# KMO_IO_MV4.net
KiCad netlist of a schematic drawn in EAGLE
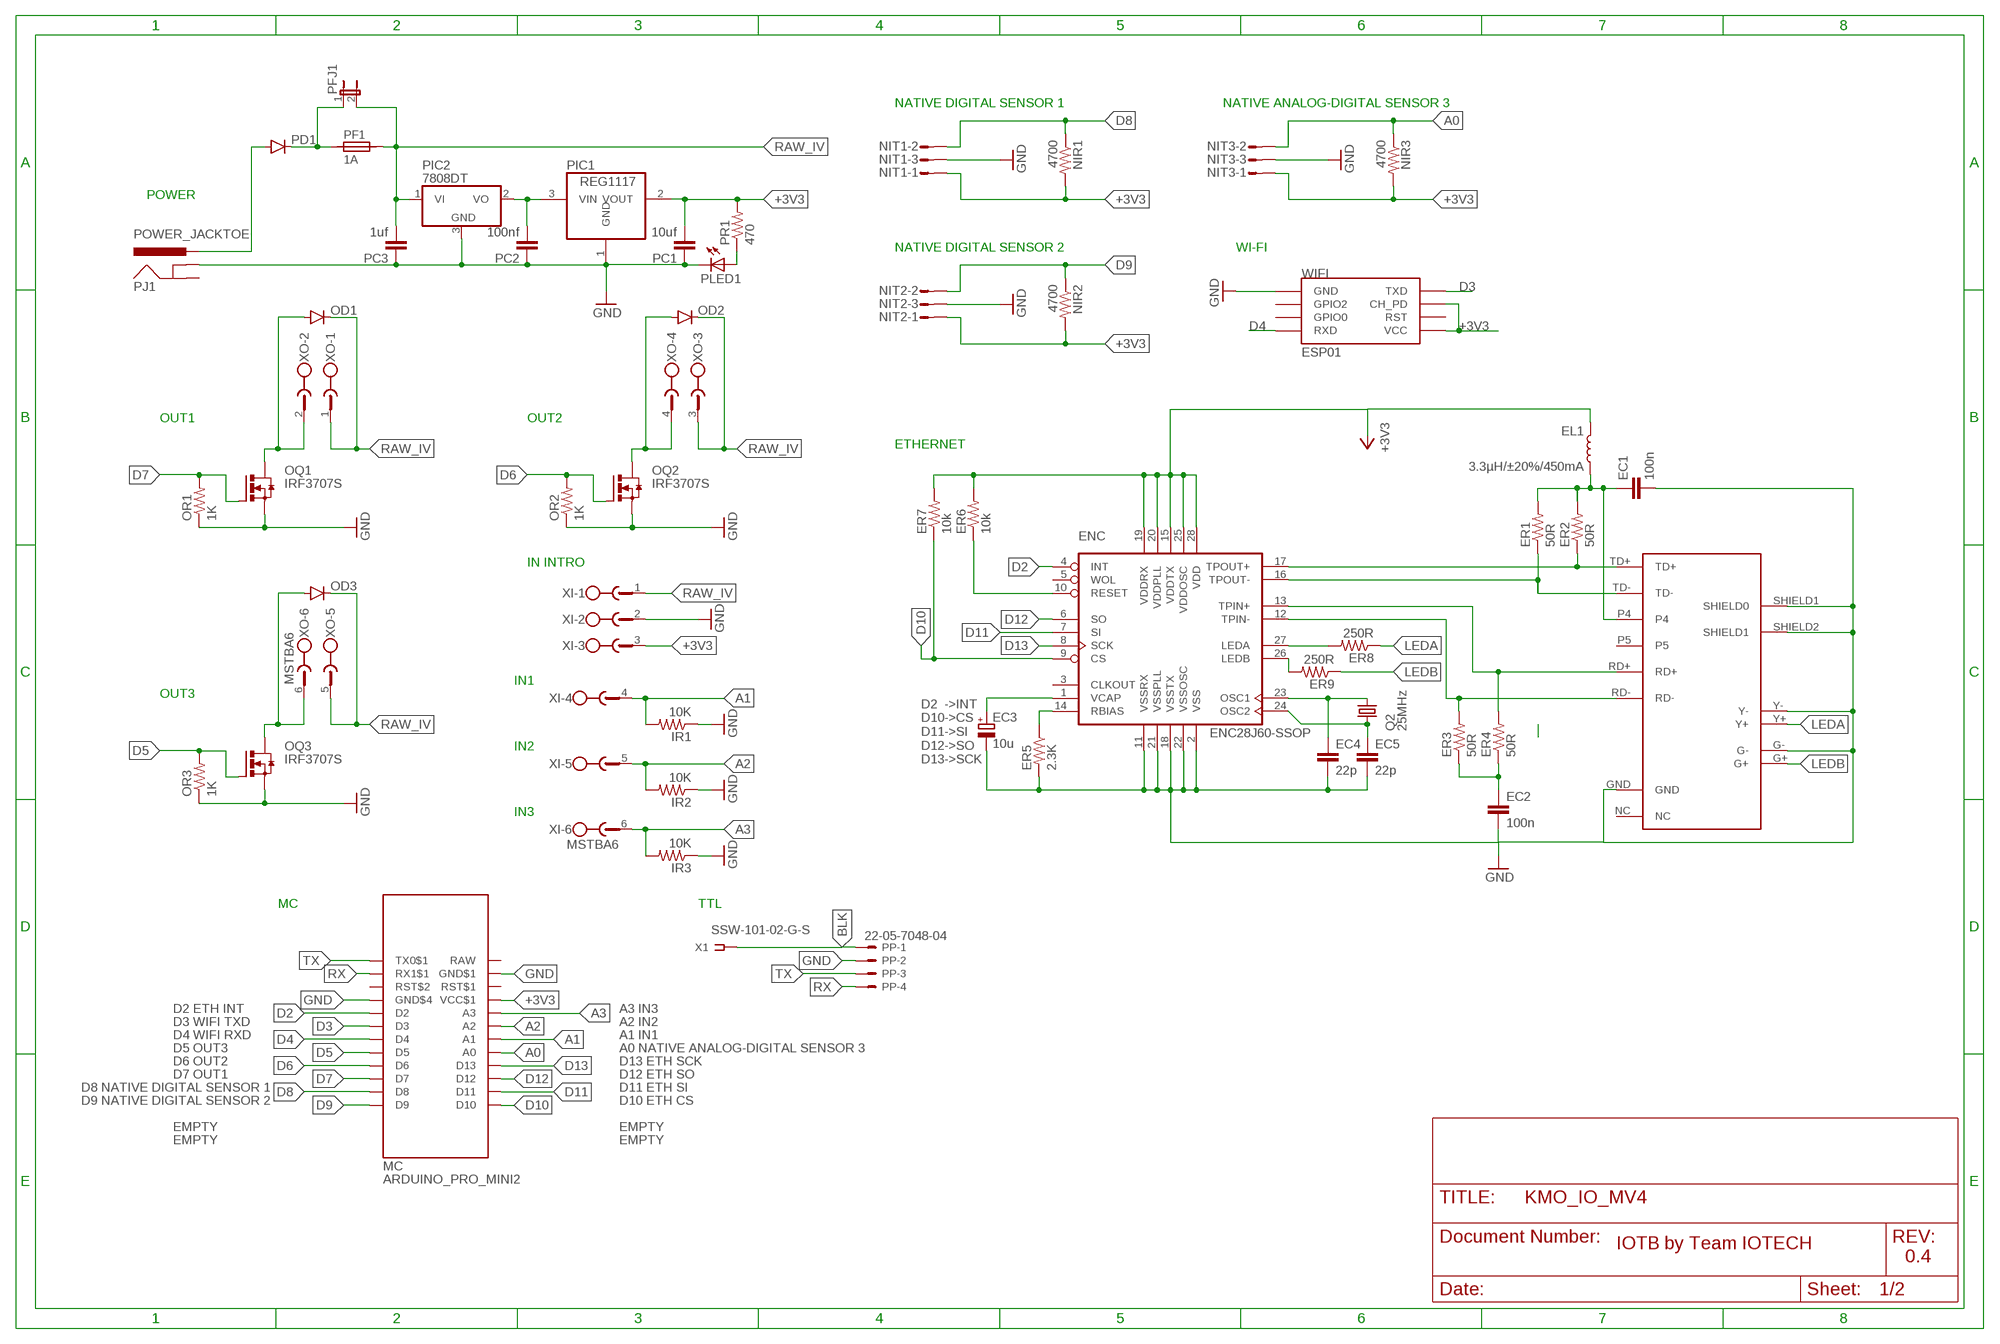
[diagram p0: schematic, sheet 1]
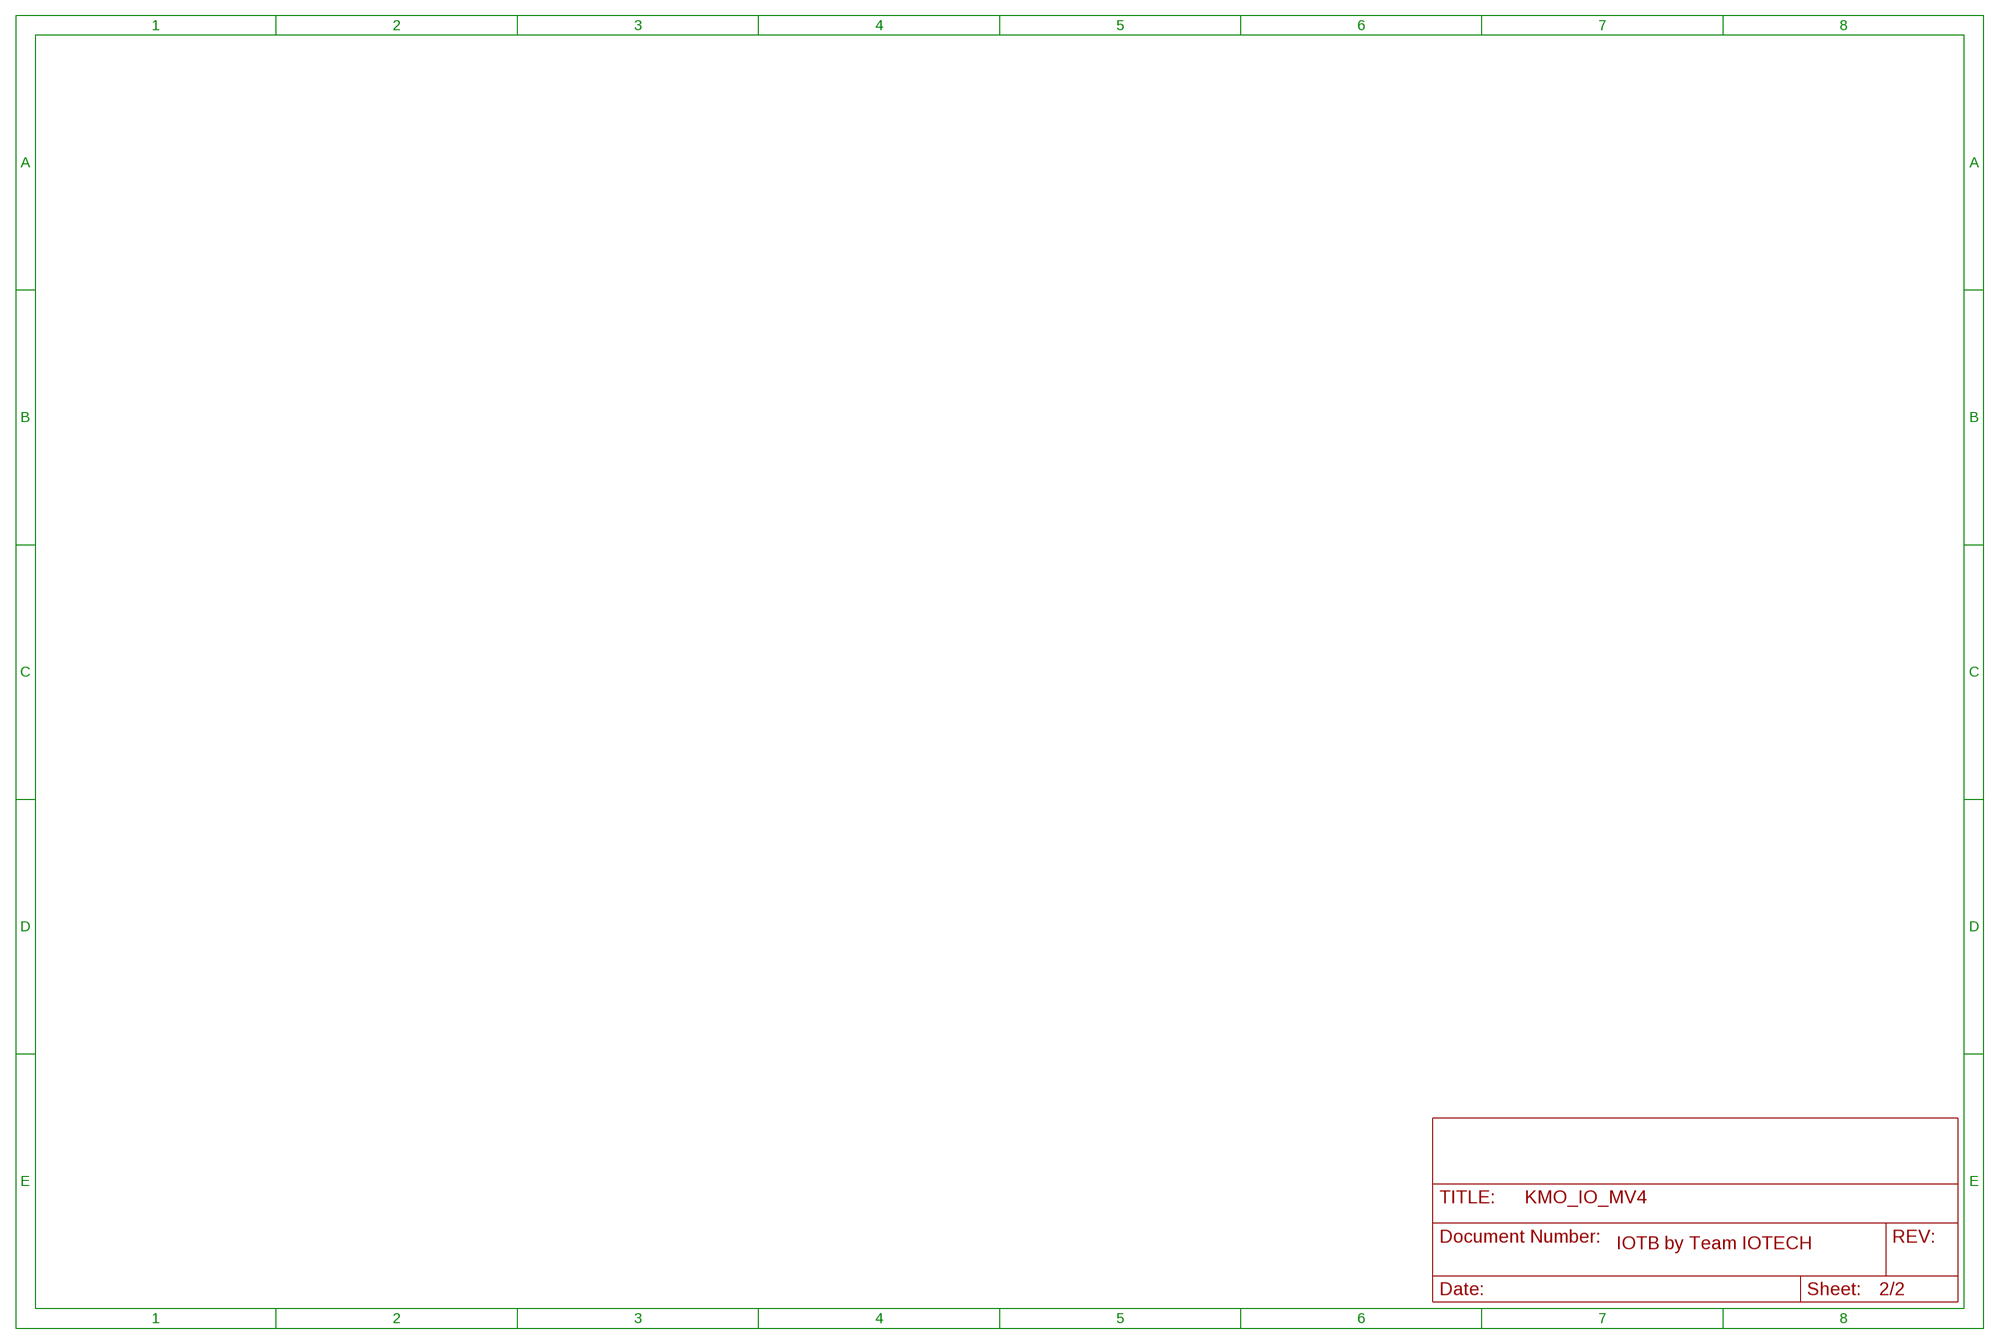
[diagram p1: schematic, sheet 2]

(export (version "E")
  (design (tool "Eeschema 10.0.6"))
  (components
    (comp (ref "EC1")
      (value "100n")
      (footprint "eagle-import:0805")
      (libsource (lib "eagle-import") (part "SparkFun-Passives_CAP0805"))
    )
    (comp (ref "EC2")
      (value "100n")
      (footprint "eagle-import:0805")
      (libsource (lib "eagle-import") (part "SparkFun-Passives_CAP0805"))
    )
    (comp (ref "EC3")
      (value "10u")
      (footprint "eagle-import:SANYO-OSCON_SMD_B6")
      (libsource (lib "eagle-import") (part "CPOL-EUSANYO_SMD_B6"))
    )
    (comp (ref "EC4")
      (value "22p")
      (footprint "eagle-import:0805")
      (libsource (lib "eagle-import") (part "SparkFun-Passives_CAP0805"))
    )
    (comp (ref "EC5")
      (value "22p")
      (footprint "eagle-import:0805")
      (libsource (lib "eagle-import") (part "SparkFun-Passives_CAP0805"))
    )
    (comp (ref "EL1")
      (value "3.3µH/±20%/450mA")
      (footprint "eagle-import:0805")
      (libsource (lib "eagle-import") (part "INDUCTOR-0805-3.3UH"))
    )
    (comp (ref "ENC")
      (value "ENC28J60-SSOP")
      (footprint "eagle-import:SSOP28")
      (libsource (lib "eagle-import") (part "ENC28J60-SSOP"))
    )
    (comp (ref "ER1")
      (value "50R")
      (footprint "eagle-import:0805")
      (libsource (lib "eagle-import") (part "RESISTOR0805-RES"))
    )
    (comp (ref "ER2")
      (value "50R")
      (footprint "eagle-import:0805")
      (libsource (lib "eagle-import") (part "RESISTOR0805-RES"))
    )
    (comp (ref "ER3")
      (value "50R")
      (footprint "eagle-import:0805")
      (libsource (lib "eagle-import") (part "RESISTOR0805-RES"))
    )
    (comp (ref "ER4")
      (value "50R")
      (footprint "eagle-import:0805")
      (libsource (lib "eagle-import") (part "RESISTOR0805-RES"))
    )
    (comp (ref "ER5")
      (value "2.3K")
      (footprint "eagle-import:0805")
      (libsource (lib "eagle-import") (part "RESISTOR0805-RES"))
    )
    (comp (ref "ER6")
      (value "10k")
      (footprint "eagle-import:0805")
      (libsource (lib "eagle-import") (part "RESISTOR0805-RES"))
    )
    (comp (ref "ER7")
      (value "10k")
      (footprint "eagle-import:0805")
      (libsource (lib "eagle-import") (part "RESISTOR0805-RES"))
    )
    (comp (ref "ER8")
      (value "250R")
      (footprint "eagle-import:0805")
      (libsource (lib "eagle-import") (part "RESISTOR0805-RES"))
    )
    (comp (ref "ER9")
      (value "250R")
      (footprint "eagle-import:0805")
      (libsource (lib "eagle-import") (part "RESISTOR0805-RES"))
    )
    (comp (ref "IR1")
      (value "10K")
      (footprint "eagle-import:0805")
      (libsource (lib "eagle-import") (part "RESISTOR0805-RES"))
    )
    (comp (ref "IR2")
      (value "10K")
      (footprint "eagle-import:0805")
      (libsource (lib "eagle-import") (part "RESISTOR0805-RES"))
    )
    (comp (ref "IR3")
      (value "10K")
      (footprint "eagle-import:0805")
      (libsource (lib "eagle-import") (part "RESISTOR0805-RES"))
    )
    (comp (ref "MC")
      (value "ARDUINO_PRO_MINI2")
      (footprint "eagle-import:ARDUINO_PRO_MINI2")
      (libsource (lib "eagle-import") (part "ARDUINO_PRO_MINI2"))
    )
    (comp (ref "NIR1")
      (value "4700")
      (footprint "eagle-import:0805")
      (libsource (lib "eagle-import") (part "RESISTOR0805-RES"))
    )
    (comp (ref "NIR2")
      (value "4700")
      (footprint "eagle-import:0805")
      (libsource (lib "eagle-import") (part "RESISTOR0805-RES"))
    )
    (comp (ref "NIR3")
      (value "4700")
      (footprint "eagle-import:0805")
      (libsource (lib "eagle-import") (part "RESISTOR0805-RES"))
    )
    (comp (ref "NIT1")
      (value "S03P")
      (footprint "eagle-import:S03P")
      (libsource (lib "eagle-import") (part "S03P"))
    )
    (comp (ref "NIT2")
      (value "S03P")
      (footprint "eagle-import:S03P")
      (libsource (lib "eagle-import") (part "S03P"))
    )
    (comp (ref "NIT3")
      (value "S03P")
      (footprint "eagle-import:S03P")
      (libsource (lib "eagle-import") (part "S03P"))
    )
    (comp (ref "OD1")
      (value "DIODESMA")
      (footprint "eagle-import:SMA-DIODE")
      (libsource (lib "eagle-import") (part "DIODESMA"))
    )
    (comp (ref "OD2")
      (value "DIODESMA")
      (footprint "eagle-import:SMA-DIODE")
      (libsource (lib "eagle-import") (part "DIODESMA"))
    )
    (comp (ref "OD3")
      (value "DIODESMA")
      (footprint "eagle-import:SMA-DIODE")
      (libsource (lib "eagle-import") (part "DIODESMA"))
    )
    (comp (ref "OQ1")
      (value "IRF3707S")
      (footprint "eagle-import:D2PACK")
      (libsource (lib "eagle-import") (part "IRF3704S"))
    )
    (comp (ref "OQ2")
      (value "IRF3707S")
      (footprint "eagle-import:D2PACK")
      (libsource (lib "eagle-import") (part "IRF3704S"))
    )
    (comp (ref "OQ3")
      (value "IRF3707S")
      (footprint "eagle-import:D2PACK")
      (libsource (lib "eagle-import") (part "IRF3704S"))
    )
    (comp (ref "OR1")
      (value "1K")
      (footprint "eagle-import:0805")
      (libsource (lib "eagle-import") (part "RESISTOR0805-RES"))
    )
    (comp (ref "OR2")
      (value "1K")
      (footprint "eagle-import:0805")
      (libsource (lib "eagle-import") (part "RESISTOR0805-RES"))
    )
    (comp (ref "OR3")
      (value "1K")
      (footprint "eagle-import:0805")
      (libsource (lib "eagle-import") (part "RESISTOR0805-RES"))
    )
    (comp (ref "PC1")
      (value "10uf")
      (footprint "eagle-import:0805")
      (libsource (lib "eagle-import") (part "CAP0805"))
    )
    (comp (ref "PC2")
      (value "100nf")
      (footprint "eagle-import:0805")
      (libsource (lib "eagle-import") (part "CAP0805"))
    )
    (comp (ref "PC3")
      (value "1uf")
      (footprint "eagle-import:0805")
      (libsource (lib "eagle-import") (part "CAP0805"))
    )
    (comp (ref "PD1")
      (value "DIODESMA")
      (footprint "eagle-import:SMA-DIODE")
      (libsource (lib "eagle-import") (part "DIODESMA"))
    )
    (comp (ref "PF1")
      (value "1A")
      (footprint "eagle-import:1820")
      (libsource (lib "eagle-import") (part "SIBA194600"))
    )
    (comp (ref "PFJ1")
      (value "JP1E")
      (footprint "eagle-import:JP1")
      (libsource (lib "eagle-import") (part "JP1E"))
    )
    (comp (ref "PIC1")
      (value "REG1117")
      (footprint "eagle-import:SOT223")
      (libsource (lib "eagle-import") (part "REG1117"))
    )
    (comp (ref "PIC2")
      (value "7808DT")
      (footprint "eagle-import:TO252")
      (libsource (lib "eagle-import") (part "78DT08"))
    )
    (comp (ref "PJ1")
      (value "POWER_JACKTOE")
      (footprint "eagle-import:POWER_JACK_SMD_OVERPASTE_TOE")
      (libsource (lib "eagle-import") (part "POWER_JACKTOE"))
    )
    (comp (ref "PLED1")
      (value "LEDCHIP-LED0805")
      (footprint "eagle-import:CHIP-LED0805")
      (libsource (lib "eagle-import") (part "LEDCHIP-LED0805"))
    )
    (comp (ref "PP")
      (value "22-05-7048-04")
      (footprint "eagle-import:7395-04")
      (fields (field (name "MF") "MOLEX"))
      (libsource (lib "eagle-import") (part "22-?-0405-7048"))
    )
    (comp (ref "PR1")
      (value "470")
      (footprint "eagle-import:0805")
      (libsource (lib "eagle-import") (part "RESISTOR0805-RES"))
    )
    (comp (ref "Q2")
      (value "25MHz")
      (footprint "eagle-import:HC49_S")
      (libsource (lib "eagle-import") (part "CRYSTALHC49S"))
    )
    (comp (ref "U$2")
      (value "HR911105A")
      (footprint "eagle-import:RJ45")
      (libsource (lib "eagle-import") (part "HR911105A"))
    )
    (comp (ref "WIFI")
      (value "ESP01")
      (footprint "eagle-import:ESP01")
      (libsource (lib "eagle-import") (part "ESP01"))
    )
    (comp (ref "X1")
      (value "SSW-101-02-G-S")
      (footprint "eagle-import:SSW-101-02-G-S")
      (fields (field (name "MF") "Samtec Inc."))
      (libsource (lib "eagle-import") (part "SSW-101-02-G-S"))
    )
    (comp (ref "XI")
      (value "MSTBA6")
      (footprint "eagle-import:MSTBA6")
      (fields (field (name "MF") "FARNELL") (field (name "MPN") "1757284"))
      (libsource (lib "eagle-import") (part "MSTBA6"))
    )
    (comp (ref "XO")
      (value "MSTBA6")
      (footprint "eagle-import:MSTBA6")
      (fields (field (name "MF") "FARNELL") (field (name "MPN") "1757284"))
      (libsource (lib "eagle-import") (part "MSTBA6"))
    )
  )
  (nets
    (net (code "1") (name "+3V3") (class "Default")
      (node (ref "EL1") (pin "1") (pinfunction "1_1") (pintype "passive"))
      (node (ref "ENC") (pin "15") (pinfunction "VDDTX_15") (pintype "power_in"))
      (node (ref "ENC") (pin "19") (pinfunction "VDDRX_19") (pintype "power_in"))
      (node (ref "ENC") (pin "20") (pinfunction "VDDPLL_20") (pintype "power_in"))
      (node (ref "ENC") (pin "25") (pinfunction "VDDOSC_25") (pintype "power_in"))
      (node (ref "ENC") (pin "28") (pinfunction "VDD_28") (pintype "power_in"))
      (node (ref "ER6") (pin "2") (pinfunction "2_2") (pintype "passive"))
      (node (ref "ER7") (pin "2") (pinfunction "2_2") (pintype "passive"))
      (node (ref "MC") (pin "VCC$1") (pinfunction "VCC$1_VCC$1") (pintype "power_in"))
      (node (ref "NIR1") (pin "2") (pinfunction "2_2") (pintype "passive"))
      (node (ref "NIR2") (pin "2") (pinfunction "2_2") (pintype "passive"))
      (node (ref "NIR3") (pin "2") (pinfunction "2_2") (pintype "passive"))
      (node (ref "NIT1") (pin "1") (pinfunction "S_1") (pintype "passive"))
      (node (ref "NIT2") (pin "1") (pinfunction "S_1") (pintype "passive"))
      (node (ref "NIT3") (pin "1") (pinfunction "S_1") (pintype "passive"))
      (node (ref "PC1") (pin "2") (pinfunction "2_2") (pintype "passive"))
      (node (ref "PIC1") (pin "2") (pinfunction "VOUT_2") (pintype "output"))
      (node (ref "PR1") (pin "2") (pinfunction "2_2") (pintype "passive"))
      (node (ref "WIFI") (pin "CH_PD") (pinfunction "CH_PD_CH_PD") (pintype "bidirectional"))
      (node (ref "WIFI") (pin "VCC") (pinfunction "VCC_VCC") (pintype "bidirectional"))
      (node (ref "XI") (pin "3") (pinfunction "1_3") (pintype "passive"))
    )
    (net (code "2") (name "A0") (class "Default")
      (node (ref "MC") (pin "A0") (pinfunction "A0_A0") (pintype "bidirectional"))
      (node (ref "NIR3") (pin "1") (pinfunction "1_1") (pintype "passive"))
      (node (ref "NIT3") (pin "2") (pinfunction "S_2") (pintype "passive"))
    )
    (net (code "3") (name "A1") (class "Default")
      (node (ref "IR1") (pin "2") (pinfunction "2_2") (pintype "passive"))
      (node (ref "MC") (pin "A1") (pinfunction "A1_A1") (pintype "bidirectional"))
      (node (ref "XI") (pin "4") (pinfunction "1_4") (pintype "passive"))
    )
    (net (code "4") (name "A2") (class "Default")
      (node (ref "IR2") (pin "2") (pinfunction "2_2") (pintype "passive"))
      (node (ref "MC") (pin "A2") (pinfunction "A2_A2") (pintype "bidirectional"))
      (node (ref "XI") (pin "5") (pinfunction "1_5") (pintype "passive"))
    )
    (net (code "5") (name "A3") (class "Default")
      (node (ref "IR3") (pin "2") (pinfunction "2_2") (pintype "passive"))
      (node (ref "MC") (pin "A3") (pinfunction "A3_A3") (pintype "bidirectional"))
      (node (ref "XI") (pin "6") (pinfunction "1_6") (pintype "passive"))
    )
    (net (code "6") (name "BLK") (class "Default")
      (node (ref "PP") (pin "1") (pinfunction "S_1") (pintype "passive"))
      (node (ref "X1") (pin "1") (pinfunction "1_1") (pintype "passive"))
    )
    (net (code "7") (name "D2") (class "Default")
      (node (ref "ENC") (pin "4") (pinfunction "INT_4") (pintype "output"))
      (node (ref "MC") (pin "D2") (pinfunction "D2_D2") (pintype "bidirectional"))
    )
    (net (code "8") (name "D3") (class "Default")
      (node (ref "MC") (pin "D3") (pinfunction "D3_D3") (pintype "bidirectional"))
      (node (ref "WIFI") (pin "TX") (pinfunction "TXD_TX") (pintype "bidirectional"))
    )
    (net (code "9") (name "D4") (class "Default")
      (node (ref "MC") (pin "D4") (pinfunction "D4_D4") (pintype "bidirectional"))
      (node (ref "WIFI") (pin "RX") (pinfunction "RXD_RX") (pintype "bidirectional"))
    )
    (net (code "10") (name "D5") (class "Default")
      (node (ref "MC") (pin "D5") (pinfunction "D5_D5") (pintype "bidirectional"))
      (node (ref "OQ3") (pin "1") (pinfunction "G_1") (pintype "passive"))
      (node (ref "OR3") (pin "2") (pinfunction "2_2") (pintype "passive"))
    )
    (net (code "11") (name "D6") (class "Default")
      (node (ref "MC") (pin "D6") (pinfunction "D6_D6") (pintype "bidirectional"))
      (node (ref "OQ2") (pin "1") (pinfunction "G_1") (pintype "passive"))
      (node (ref "OR2") (pin "2") (pinfunction "2_2") (pintype "passive"))
    )
    (net (code "12") (name "D7") (class "Default")
      (node (ref "MC") (pin "D7") (pinfunction "D7_D7") (pintype "bidirectional"))
      (node (ref "OQ1") (pin "1") (pinfunction "G_1") (pintype "passive"))
      (node (ref "OR1") (pin "2") (pinfunction "2_2") (pintype "passive"))
    )
    (net (code "13") (name "D8") (class "Default")
      (node (ref "MC") (pin "D8") (pinfunction "D8_D8") (pintype "bidirectional"))
      (node (ref "NIR1") (pin "1") (pinfunction "1_1") (pintype "passive"))
      (node (ref "NIT1") (pin "2") (pinfunction "S_2") (pintype "passive"))
    )
    (net (code "14") (name "D9") (class "Default")
      (node (ref "MC") (pin "D9") (pinfunction "D9_D9") (pintype "bidirectional"))
      (node (ref "NIR2") (pin "1") (pinfunction "1_1") (pintype "passive"))
      (node (ref "NIT2") (pin "2") (pinfunction "S_2") (pintype "passive"))
    )
    (net (code "15") (name "D10") (class "Default")
      (node (ref "ENC") (pin "9") (pinfunction "CS_9") (pintype "input"))
      (node (ref "ER7") (pin "1") (pinfunction "1_1") (pintype "passive"))
      (node (ref "MC") (pin "D10") (pinfunction "D10_D10") (pintype "bidirectional"))
    )
    (net (code "16") (name "D11") (class "Default")
      (node (ref "ENC") (pin "7") (pinfunction "SI_7") (pintype "input"))
      (node (ref "MC") (pin "D11") (pinfunction "D11_D11") (pintype "bidirectional"))
    )
    (net (code "17") (name "D12") (class "Default")
      (node (ref "ENC") (pin "6") (pinfunction "SO_6") (pintype "output"))
      (node (ref "MC") (pin "D12") (pinfunction "D12_D12") (pintype "bidirectional"))
    )
    (net (code "18") (name "D13") (class "Default")
      (node (ref "ENC") (pin "8") (pinfunction "SCK_8") (pintype "input"))
      (node (ref "MC") (pin "D13") (pinfunction "D13_D13") (pintype "bidirectional"))
    )
    (net (code "19") (name "GND") (class "Default")
      (node (ref "EC1") (pin "2") (pinfunction "2_2") (pintype "passive"))
      (node (ref "EC2") (pin "2") (pinfunction "2_2") (pintype "passive"))
      (node (ref "EC3") (pin "-") (pinfunction "-_-") (pintype "passive"))
      (node (ref "EC4") (pin "2") (pinfunction "2_2") (pintype "passive"))
      (node (ref "EC5") (pin "2") (pinfunction "2_2") (pintype "passive"))
      (node (ref "ENC") (pin "11") (pinfunction "VSSRX_11") (pintype "power_in"))
      (node (ref "ENC") (pin "18") (pinfunction "VSSTX_18") (pintype "power_in"))
      (node (ref "ENC") (pin "2") (pinfunction "VSS_2") (pintype "power_in"))
      (node (ref "ENC") (pin "21") (pinfunction "VSSPLL_21") (pintype "power_in"))
      (node (ref "ENC") (pin "22") (pinfunction "VSSOSC_22") (pintype "power_in"))
      (node (ref "ER5") (pin "2") (pinfunction "2_2") (pintype "passive"))
      (node (ref "IR1") (pin "1") (pinfunction "1_1") (pintype "passive"))
      (node (ref "IR2") (pin "1") (pinfunction "1_1") (pintype "passive"))
      (node (ref "IR3") (pin "1") (pinfunction "1_1") (pintype "passive"))
      (node (ref "MC") (pin "GDN$1") (pinfunction "GND$1_GDN$1") (pintype "power_in"))
      (node (ref "MC") (pin "GND$4") (pinfunction "GND$4_GND$4") (pintype "power_in"))
      (node (ref "NIT1") (pin "3") (pinfunction "S_3") (pintype "passive"))
      (node (ref "NIT2") (pin "3") (pinfunction "S_3") (pintype "passive"))
      (node (ref "NIT3") (pin "3") (pinfunction "S_3") (pintype "passive"))
      (node (ref "OQ1") (pin "3") (pinfunction "S_3") (pintype "passive"))
      (node (ref "OQ2") (pin "3") (pinfunction "S_3") (pintype "passive"))
      (node (ref "OQ3") (pin "3") (pinfunction "S_3") (pintype "passive"))
      (node (ref "OR1") (pin "1") (pinfunction "1_1") (pintype "passive"))
      (node (ref "OR2") (pin "1") (pinfunction "1_1") (pintype "passive"))
      (node (ref "OR3") (pin "1") (pinfunction "1_1") (pintype "passive"))
      (node (ref "PC1") (pin "1") (pinfunction "1_1") (pintype "passive"))
      (node (ref "PC2") (pin "1") (pinfunction "1_1") (pintype "passive"))
      (node (ref "PC3") (pin "1") (pinfunction "1_1") (pintype "passive"))
      (node (ref "PIC1") (pin "1") (pinfunction "GND_1") (pintype "power_in"))
      (node (ref "PIC2") (pin "3") (pinfunction "GND_3") (pintype "passive"))
      (node (ref "PJ1") (pin "GND") (pinfunction "GNDBREAK_GND") (pintype "bidirectional"))
      (node (ref "PLED1") (pin "C") (pinfunction "C_C") (pintype "passive"))
      (node (ref "PP") (pin "2") (pinfunction "S_2") (pintype "passive"))
      (node (ref "U$2") (pin "G-") (pinfunction "G-_G-") (pintype "bidirectional"))
      (node (ref "U$2") (pin "GND") (pinfunction "GND_GND") (pintype "bidirectional"))
      (node (ref "U$2") (pin "SHIELD1") (pinfunction "SHIELD0_SHIELD1") (pintype "bidirectional"))
      (node (ref "U$2") (pin "SHIELD2") (pinfunction "SHIELD1_SHIELD2") (pintype "bidirectional"))
      (node (ref "U$2") (pin "Y-") (pinfunction "Y-_Y-") (pintype "bidirectional"))
      (node (ref "WIFI") (pin "GND") (pinfunction "GND_GND") (pintype "bidirectional"))
      (node (ref "XI") (pin "2") (pinfunction "1_2") (pintype "passive"))
    )
    (net (code "20") (name "LEDA") (class "Default")
      (node (ref "ER8") (pin "1") (pinfunction "1_1") (pintype "passive"))
      (node (ref "U$2") (pin "Y+") (pinfunction "Y+_Y+") (pintype "bidirectional"))
    )
    (net (code "21") (name "LEDB") (class "Default")
      (node (ref "ER9") (pin "1") (pinfunction "1_1") (pintype "passive"))
      (node (ref "U$2") (pin "G+") (pinfunction "G+_G+") (pintype "bidirectional"))
    )
    (net (code "22") (name "Net-(EC1-Pad1)") (class "Default")
      (node (ref "EC1") (pin "1") (pinfunction "1_1") (pintype "passive"))
      (node (ref "EL1") (pin "2") (pinfunction "2_2") (pintype "passive"))
      (node (ref "ER1") (pin "2") (pinfunction "2_2") (pintype "passive"))
      (node (ref "ER2") (pin "2") (pinfunction "2_2") (pintype "passive"))
      (node (ref "U$2") (pin "P4") (pinfunction "P4_P4") (pintype "bidirectional"))
    )
    (net (code "23") (name "Net-(EC2-Pad1)") (class "Default")
      (node (ref "EC2") (pin "1") (pinfunction "1_1") (pintype "passive"))
      (node (ref "ER3") (pin "1") (pinfunction "1_1") (pintype "passive"))
      (node (ref "ER4") (pin "1") (pinfunction "1_1") (pintype "passive"))
    )
    (net (code "24") (name "Net-(ENC-LEDA)") (class "Default")
      (node (ref "ENC") (pin "27") (pinfunction "LEDA_27") (pintype "output"))
      (node (ref "ER8") (pin "2") (pinfunction "2_2") (pintype "passive"))
    )
    (net (code "25") (name "Net-(ENC-LEDB)") (class "Default")
      (node (ref "ENC") (pin "26") (pinfunction "LEDB_26") (pintype "output"))
      (node (ref "ER9") (pin "2") (pinfunction "2_2") (pintype "passive"))
    )
    (net (code "26") (name "Net-(ENC-OSC1)") (class "Default")
      (node (ref "EC4") (pin "1") (pinfunction "1_1") (pintype "passive"))
      (node (ref "ENC") (pin "23") (pinfunction "OSC1_23") (pintype "input"))
      (node (ref "Q2") (pin "2") (pinfunction "2_2") (pintype "passive"))
    )
    (net (code "27") (name "Net-(ENC-OSC2)") (class "Default")
      (node (ref "EC5") (pin "1") (pinfunction "1_1") (pintype "passive"))
      (node (ref "ENC") (pin "24") (pinfunction "OSC2_24") (pintype "output"))
      (node (ref "Q2") (pin "1") (pinfunction "1_1") (pintype "passive"))
    )
    (net (code "28") (name "Net-(ENC-RBIAS)") (class "Default")
      (node (ref "ENC") (pin "14") (pinfunction "RBIAS_14") (pintype "passive"))
      (node (ref "ER5") (pin "1") (pinfunction "1_1") (pintype "passive"))
    )
    (net (code "29") (name "Net-(ENC-RESET)") (class "Default")
      (node (ref "ENC") (pin "10") (pinfunction "RESET_10") (pintype "input"))
      (node (ref "ER6") (pin "1") (pinfunction "1_1") (pintype "passive"))
    )
    (net (code "30") (name "Net-(ENC-TPIN+)") (class "Default")
      (node (ref "ENC") (pin "13") (pinfunction "TPIN+_13") (pintype "input"))
      (node (ref "ER4") (pin "2") (pinfunction "2_2") (pintype "passive"))
      (node (ref "U$2") (pin "RD+") (pinfunction "RD+_RD+") (pintype "bidirectional"))
    )
    (net (code "31") (name "Net-(ENC-TPIN-)") (class "Default")
      (node (ref "ENC") (pin "12") (pinfunction "TPIN-_12") (pintype "input"))
      (node (ref "ER3") (pin "2") (pinfunction "2_2") (pintype "passive"))
      (node (ref "U$2") (pin "RD-") (pinfunction "RD-_RD-") (pintype "bidirectional"))
    )
    (net (code "32") (name "Net-(ENC-TPOUT+)") (class "Default")
      (node (ref "ENC") (pin "17") (pinfunction "TPOUT+_17") (pintype "output"))
      (node (ref "ER2") (pin "1") (pinfunction "1_1") (pintype "passive"))
      (node (ref "U$2") (pin "TD+") (pinfunction "TD+_TD+") (pintype "bidirectional"))
    )
    (net (code "33") (name "Net-(ENC-TPOUT-)") (class "Default")
      (node (ref "ENC") (pin "16") (pinfunction "TPOUT-_16") (pintype "output"))
      (node (ref "ER1") (pin "1") (pinfunction "1_1") (pintype "passive"))
      (node (ref "U$2") (pin "TD-") (pinfunction "TD-_TD-") (pintype "bidirectional"))
    )
    (net (code "34") (name "Net-(ENC-VCAP)") (class "Default")
      (node (ref "EC3") (pin "+") (pinfunction "+_+") (pintype "passive"))
      (node (ref "ENC") (pin "1") (pinfunction "VCAP_1") (pintype "power_in"))
    )
    (net (code "35") (name "Net-(OQ1-D)") (class "Default")
      (node (ref "OD1") (pin "A") (pinfunction "A_A") (pintype "passive"))
      (node (ref "OQ1") (pin "2") (pinfunction "D_2") (pintype "passive"))
      (node (ref "XO") (pin "2") (pinfunction "1_2") (pintype "passive"))
    )
    (net (code "36") (name "Net-(OQ2-D)") (class "Default")
      (node (ref "OD2") (pin "A") (pinfunction "A_A") (pintype "passive"))
      (node (ref "OQ2") (pin "2") (pinfunction "D_2") (pintype "passive"))
      (node (ref "XO") (pin "4") (pinfunction "1_4") (pintype "passive"))
    )
    (net (code "37") (name "Net-(OQ3-D)") (class "Default")
      (node (ref "OD3") (pin "A") (pinfunction "A_A") (pintype "passive"))
      (node (ref "OQ3") (pin "2") (pinfunction "D_2") (pintype "passive"))
      (node (ref "XO") (pin "6") (pinfunction "1_6") (pintype "passive"))
    )
    (net (code "38") (name "Net-(PD1-PadC)") (class "Default")
      (node (ref "PD1") (pin "C") (pinfunction "C_C") (pintype "passive"))
      (node (ref "PF1") (pin "1") (pinfunction "1_1") (pintype "passive"))
      (node (ref "PFJ1") (pin "1") (pinfunction "1_1") (pintype "passive"))
    )
    (net (code "39") (name "Net-(PIC1-VIN)") (class "Default")
      (node (ref "PC2") (pin "2") (pinfunction "2_2") (pintype "passive"))
      (node (ref "PIC1") (pin "3") (pinfunction "VIN_3") (pintype "input"))
      (node (ref "PIC2") (pin "2") (pinfunction "VO_2") (pintype "passive"))
    )
    (net (code "40") (name "Net-(PJ1-PWR)") (class "Default")
      (node (ref "PD1") (pin "A") (pinfunction "A_A") (pintype "passive"))
      (node (ref "PJ1") (pin "VIN0") (pinfunction "PWR_VIN0") (pintype "bidirectional"))
    )
    (net (code "41") (name "Net-(PLED1-PadA)") (class "Default")
      (node (ref "PLED1") (pin "A") (pinfunction "A_A") (pintype "passive"))
      (node (ref "PR1") (pin "1") (pinfunction "1_1") (pintype "passive"))
    )
    (net (code "42") (name "RAW") (class "Default")
      (node (ref "MC") (pin "RAW") (pinfunction "RAW_RAW") (pintype "power_in"))
    )
    (net (code "43") (name "RAW_IV") (class "Default")
      (node (ref "OD1") (pin "C") (pinfunction "C_C") (pintype "passive"))
      (node (ref "OD2") (pin "C") (pinfunction "C_C") (pintype "passive"))
      (node (ref "OD3") (pin "C") (pinfunction "C_C") (pintype "passive"))
      (node (ref "PC3") (pin "2") (pinfunction "2_2") (pintype "passive"))
      (node (ref "PF1") (pin "2") (pinfunction "2_2") (pintype "passive"))
      (node (ref "PFJ1") (pin "2") (pinfunction "2_2") (pintype "passive"))
      (node (ref "PIC2") (pin "1") (pinfunction "VI_1") (pintype "input"))
      (node (ref "XI") (pin "1") (pinfunction "1_1") (pintype "passive"))
      (node (ref "XO") (pin "1") (pinfunction "1_1") (pintype "passive"))
      (node (ref "XO") (pin "3") (pinfunction "1_3") (pintype "passive"))
      (node (ref "XO") (pin "5") (pinfunction "1_5") (pintype "passive"))
    )
    (net (code "44") (name "RX") (class "Default")
      (node (ref "MC") (pin "RX1$1") (pinfunction "RX1$1_RX1$1") (pintype "bidirectional"))
      (node (ref "PP") (pin "4") (pinfunction "S_4") (pintype "passive"))
    )
    (net (code "45") (name "TX") (class "Default")
      (node (ref "MC") (pin "TX0$1") (pinfunction "TX0$1_TX0$1") (pintype "bidirectional"))
      (node (ref "PP") (pin "3") (pinfunction "S_3") (pintype "passive"))
    )
    (net (code "46") (name "unconnected-(ENC-CLKOUT-Pad3)") (class "Default")
      (node (ref "ENC") (pin "3") (pinfunction "CLKOUT_3") (pintype "output"))
    )
    (net (code "47") (name "unconnected-(ENC-WOL-Pad5)") (class "Default")
      (node (ref "ENC") (pin "5") (pinfunction "WOL_5") (pintype "output"))
    )
    (net (code "48") (name "unconnected-(MC-PadRST$1)") (class "Default")
      (node (ref "MC") (pin "RST$1") (pinfunction "RST$1_RST$1") (pintype "input"))
    )
    (net (code "49") (name "unconnected-(MC-PadRST$2)") (class "Default")
      (node (ref "MC") (pin "RST$2") (pinfunction "RST$2_RST$2") (pintype "input"))
    )
    (net (code "50") (name "unconnected-(PJ1-GND-PadP$4)") (class "Default")
      (node (ref "PJ1") (pin "P$4") (pinfunction "GND_P$4") (pintype "bidirectional"))
    )
    (net (code "51") (name "unconnected-(U$2-PadNC)") (class "Default")
      (node (ref "U$2") (pin "NC") (pinfunction "NC_NC") (pintype "bidirectional"))
    )
    (net (code "52") (name "unconnected-(U$2-PadP5)") (class "Default")
      (node (ref "U$2") (pin "P5") (pinfunction "P5_P5") (pintype "bidirectional"))
    )
    (net (code "53") (name "unconnected-(WIFI-PadGPIO0)") (class "Default")
      (node (ref "WIFI") (pin "GPIO0") (pinfunction "GPIO0_GPIO0") (pintype "bidirectional"))
    )
    (net (code "54") (name "unconnected-(WIFI-PadGPIO2)") (class "Default")
      (node (ref "WIFI") (pin "GPIO2") (pinfunction "GPIO2_GPIO2") (pintype "bidirectional"))
    )
    (net (code "55") (name "unconnected-(WIFI-PadRST)") (class "Default")
      (node (ref "WIFI") (pin "RST") (pinfunction "RST_RST") (pintype "bidirectional"))
    )
  )
)
